# Modified_Dub_Siren.net
KiCad netlist of a schematic drawn in Altium Designer
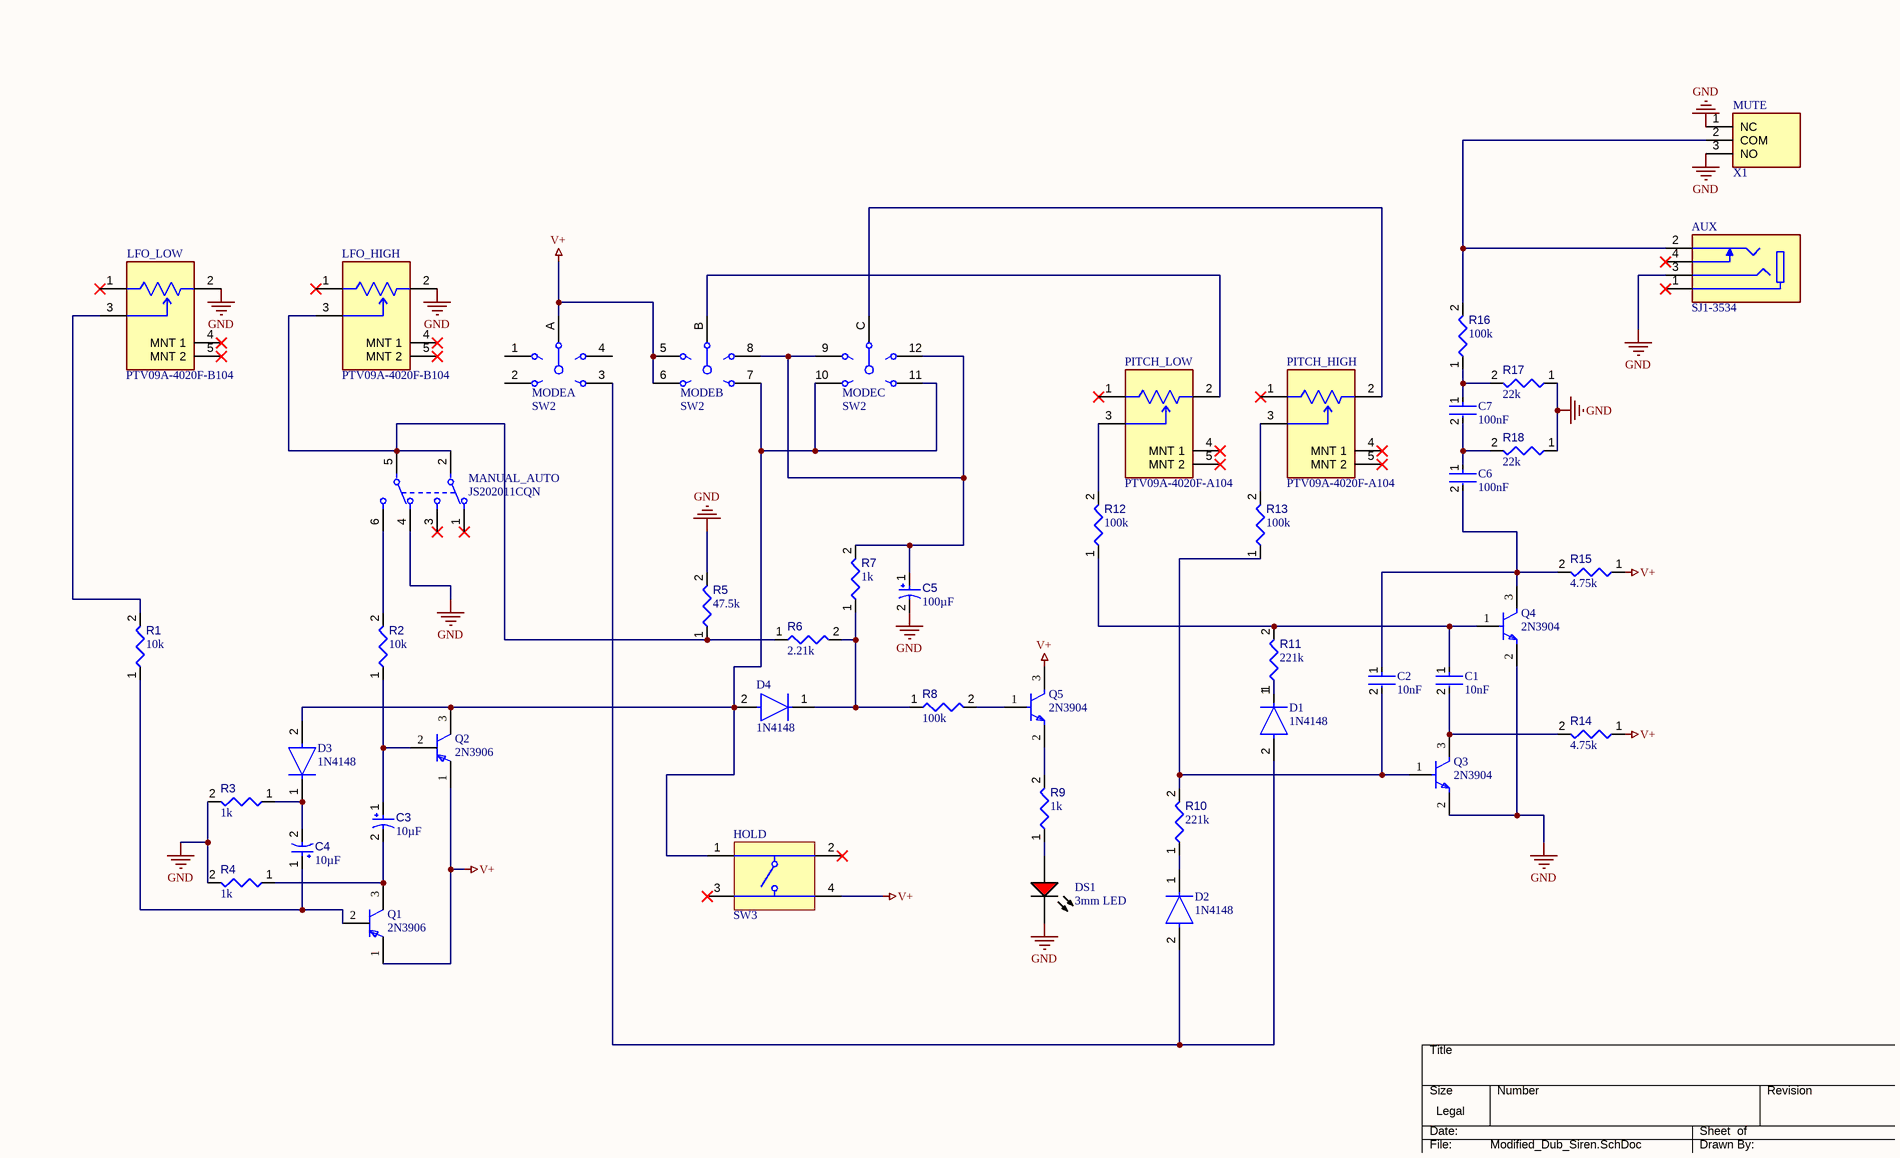
[diagram p0: Modified_Dub_Siren.SchDoc]

(export (version "E")
  (design (tool "Eeschema 10.0.6"))
  (components
    (comp (ref "AUX")
      (value "SJ1-3534")
      (footprint "CUI_SJ1-3533")
      (description "3.5 mm Right-Angle Stereo Jack, 4 Pin PCB Mount, Threaded w/ Nut")
      (fields (field (name "MF") "Same Sky"))
      (libsource (lib "SJ1-3534") (part "SJ1-3534"))
    )
    (comp (ref "C1")
      (value "10nF")
      (footprint "FP-K15H5-MFG")
      (description "CAP CER 0.1UF 50V X7R RADIAL")
      (fields (field (name "VOLTAGE") "50V") (field (name "TOLERANCE") "10%"))
      (libsource (lib "Altium Content Vault") (part "11868f565c42a9108669ba33697ecf6"))
    )
    (comp (ref "C2")
      (value "10nF")
      (footprint "FP-K15H5-MFG")
      (description "CAP CER 0.1UF 50V X7R RADIAL")
      (fields (field (name "VOLTAGE") "50V") (field (name "TOLERANCE") "10%"))
      (libsource (lib "Altium Content Vault") (part "11868f565c42a9108669ba33697ecf6"))
    )
    (comp (ref "C3")
      (value "10µF")
      (footprint "CAPPR55-200-1100X500X1200")
      (description "Aluminum Electrolytic Capacitor, 10 uF, +/- 20%, 50 V, -40 to 85 degC, 2-Pin THD, RoHS, Bulk")
      (fields (field (name "MANUFACTURER") "Panasonic") (field (name "TOLERANCE") "20%"))
      (libsource (lib "Brenna Kennedy-Moore") (part "CAP-P-2"))
    )
    (comp (ref "C4")
      (value "10µF")
      (footprint "CAPPR55-200-1100X500X1200")
      (description "Aluminum Electrolytic Capacitor, 10 uF, +/- 20%, 50 V, -40 to 85 degC, 2-Pin THD, RoHS, Bulk")
      (fields (field (name "MANUFACTURER") "Panasonic") (field (name "TOLERANCE") "20%"))
      (libsource (lib "") (part "CAP-P-2_1"))
    )
    (comp (ref "C5")
      (value "100µF")
      (footprint "CAPPR55-200-1100X500X1200")
      (description "Aluminum Electrolytic Capacitor, 10 uF, +/- 20%, 50 V, -40 to 85 degC, 2-Pin THD, RoHS, Bulk")
      (fields (field (name "MANUFACTURER") "Panasonic") (field (name "TOLERANCE") "20%"))
      (libsource (lib "Brenna Kennedy-Moore") (part "CAP-P-2"))
    )
    (comp (ref "C6")
      (value "100nF")
      (footprint "FP-K15H5-MFG")
      (description "CAP CER 0.1UF 50V X7R RADIAL")
      (fields (field (name "VOLTAGE") "50V") (field (name "TOLERANCE") "10%"))
      (libsource (lib "Altium Content Vault") (part "11868f565c42a9108669ba33697ecf6"))
    )
    (comp (ref "C7")
      (value "100nF")
      (footprint "FP-K15H5-MFG")
      (description "CAP CER 0.1UF 50V X7R RADIAL")
      (fields (field (name "VOLTAGE") "50V") (field (name "TOLERANCE") "10%"))
      (libsource (lib "Altium Content Vault") (part "11868f565c42a9108669ba33697ecf6"))
    )
    (comp (ref "D1")
      (value "1N4148")
      (footprint "FP-017AG-MFG")
      (description "DIODE GEN PURP 100V 200MA DO35")
      (fields (field (name "VOLTAGE") "100V"))
      (libsource (lib "Altium Content Vault") (part "d7152d700b627762746794eb795d46e"))
    )
    (comp (ref "D2")
      (value "1N4148")
      (footprint "FP-017AG-MFG")
      (description "DIODE GEN PURP 100V 200MA DO35")
      (fields (field (name "VOLTAGE") "100V"))
      (libsource (lib "Altium Content Vault") (part "d7152d700b627762746794eb795d46e"))
    )
    (comp (ref "D3")
      (value "1N4148")
      (footprint "FP-017AG-MFG")
      (description "DIODE GEN PURP 100V 200MA DO35")
      (fields (field (name "VOLTAGE") "100V"))
      (libsource (lib "Altium Content Vault") (part "d7152d700b627762746794eb795d46e"))
    )
    (comp (ref "D4")
      (value "1N4148")
      (footprint "FP-017AG-MFG")
      (description "DIODE GEN PURP 100V 200MA DO35")
      (fields (field (name "VOLTAGE") "100V"))
      (libsource (lib "Altium Content Vault") (part "d7152d700b627762746794eb795d46e"))
    )
    (comp (ref "DS1")
      (value "3mm LED")
      (footprint "LED-2P-2.28-3MM_A")
      (description "Red LED, 80 mW, 30 mA, -25 to 85 degC, 2-Pin THD")
      (fields (field (name "MANUFACTURER") "Shenzhen CGX"))
      (libsource (lib "Brenna Kennedy-Moore") (part "LED-RED-AK-2"))
    )
    (comp (ref "HOLD")
      (value "SW3")
      (footprint "BEST-TS-1109_V")
      (description "Tactile Switch, SPST, 12 V, 50 mA, -20 to 80 degC, 4-Pin THD")
      (fields (field (name "MANUFACTURER") "Shenzhen Best"))
      (libsource (lib "Brenna Kennedy-Moore") (part "SW-SPST-4_A"))
    )
    (comp (ref "LFO_HIGH")
      (value "PTV09A-4020F-B104")
      (footprint "FP-PTV09A-4020-MFG")
      (description "POT 20K OHM 1/20W CARBON LOG")
      (fields
        (field (name "TOLERANCE") "20%")
        (field (name "OCTOPART") "https://octopart.com/ptv09a-4020f-a203-bourns-1637636")
      )
      (libsource (lib "Altium Content Vault") (part "93b1c08ba1369577c2f09b47e9e292e"))
    )
    (comp (ref "LFO_LOW")
      (value "PTV09A-4020F-B104")
      (footprint "FP-PTV09A-4020-MFG")
      (description "POT 20K OHM 1/20W CARBON LOG")
      (fields
        (field (name "TOLERANCE") "20%")
        (field (name "OCTOPART") "https://octopart.com/ptv09a-4020f-a203-bourns-1637636")
      )
      (libsource (lib "Altium Content Vault") (part "93b1c08ba1369577c2f09b47e9e292e"))
    )
    (comp (ref "MANUAL_AUTO")
      (value "JS202011CQN")
      (footprint "FP-JS202011AQN-MFG")
      (description "SWITCH SLIDE DPDT 300MA 6V")
      (libsource (lib "Altium Content Vault") (part "a9e2ad50e97b660f430b512a9354c8c"))
    )
    (comp (ref "MODE")
      (value "SW2")
      (footprint "CKCP-A30415RNZQ-15_V")
      (description "A Series Rotary Switch, 3 Poles, 4 Positions, 30 deg Angle of Throw, -30 to 85 degC, RoHS")
      (fields (field (name "PARTNUMBER") "A30415RNZQE") (field (name "MANUFACTURER") "C&K Components"))
      (libsource (lib "Altium Content Vault") (part "CKCP-SW_3P4T-15"))
    )
    (comp (ref "MUTE")
      (value "X1")
      (footprint "100SP5T1B1M2QEH")
      (description "TOGGLE, 5A, 120VAC/28VDC SPDT, On-Off-(On) Panel Mount, Through Hole")
      (fields
        (field (name "MANUFACTURER_PART_NUMBER") "100SP5T1B1M2QEH")
        (field (name "MOUSER PART NUMBER") "612-100-E1121")
      )
      (libsource (lib "100SP5T1B1M2QEH") (part "100SP5T1B1M2QEH"))
    )
    (comp (ref "PITCH_HIGH")
      (value "PTV09A-4020F-A104")
      (footprint "FP-PTV09A-4020-MFG")
      (description "POT 20K OHM 1/20W CARBON LOG")
      (fields
        (field (name "TOLERANCE") "20%")
        (field (name "OCTOPART") "https://octopart.com/ptv09a-4020f-a203-bourns-1637636")
      )
      (libsource (lib "Altium Content Vault") (part "93b1c08ba1369577c2f09b47e9e292e"))
    )
    (comp (ref "PITCH_LOW")
      (value "PTV09A-4020F-A104")
      (footprint "FP-PTV09A-4020-MFG")
      (description "POT 20K OHM 1/20W CARBON LOG")
      (fields
        (field (name "TOLERANCE") "20%")
        (field (name "OCTOPART") "https://octopart.com/ptv09a-4020f-a203-bourns-1637636")
      )
      (libsource (lib "Altium Content Vault") (part "93b1c08ba1369577c2f09b47e9e292e"))
    )
    (comp (ref "Q1")
      (value "2N3906")
      (footprint "FP-135AR-MFG")
      (description "2N3906TF Small Signal Bipolar Transistor, 0.2A I(C), 40V V(BR)CEO, 1-Element, PNP, Silicon, TO-92")
      (libsource (lib "Altium Content Vault") (part "40d2b7e180a7bcff784209620afba3e"))
    )
    (comp (ref "Q2")
      (value "2N3906")
      (footprint "FP-135AR-MFG")
      (description "2N3906TF Small Signal Bipolar Transistor, 0.2A I(C), 40V V(BR)CEO, 1-Element, PNP, Silicon, TO-92")
      (libsource (lib "Altium Content Vault") (part "40d2b7e180a7bcff784209620afba3e"))
    )
    (comp (ref "Q3")
      (value "2N3904")
      (footprint "FP-135AR-MFG")
      (description "KSP10TA Transistor, bjt, npn, 25V V(Br)Ceo, to-92 Rohs Compliant: Yes")
      (libsource (lib "Altium Content Vault") (part "b44e953556f554d0102664c7d152cb4"))
    )
    (comp (ref "Q4")
      (value "2N3904")
      (footprint "FP-135AR-MFG")
      (description "KSP10TA Transistor, bjt, npn, 25V V(Br)Ceo, to-92 Rohs Compliant: Yes")
      (libsource (lib "Altium Content Vault") (part "b44e953556f554d0102664c7d152cb4"))
    )
    (comp (ref "Q5")
      (value "2N3904")
      (footprint "FP-135AR-MFG")
      (description "KSP10TA Transistor, bjt, npn, 25V V(Br)Ceo, to-92 Rohs Compliant: Yes")
      (libsource (lib "Altium Content Vault") (part "b44e953556f554d0102664c7d152cb4"))
    )
    (comp (ref "R1")
      (value "10k")
      (footprint "RESA60-630X240")
      (description "Axial Resistor, 10 KOhm, +/- 1%, 0.25 W, -55 to 155 degC, 2-Pin THD, RoHS, Bulk")
      (fields (field (name "POWER") "250mW") (field (name "TOLERANCE") "1%"))
      (libsource (lib "Brenna Kennedy-Moore") (part "RES-2"))
    )
    (comp (ref "R2")
      (value "10k")
      (footprint "RESA60-630X240")
      (description "Axial Resistor, 10 KOhm, +/- 1%, 0.25 W, -55 to 155 degC, 2-Pin THD, RoHS, Bulk")
      (fields (field (name "POWER") "250mW") (field (name "TOLERANCE") "1%"))
      (libsource (lib "Brenna Kennedy-Moore") (part "RES-2"))
    )
    (comp (ref "R3")
      (value "1k")
      (footprint "RESA60-630X240")
      (description "Axial Resistor, 1 KOhm, +/- 1%, 250 mW, -55 to 155 degC, 2-Pin THD, RoHS, Bulk")
      (fields (field (name "POWER") "250mW") (field (name "TOLERANCE") "1%"))
      (libsource (lib "Brenna Kennedy-Moore") (part "RES-2"))
    )
    (comp (ref "R4")
      (value "1k")
      (footprint "RESA60-630X240")
      (description "Axial Resistor, 1 KOhm, +/- 1%, 250 mW, -55 to 155 degC, 2-Pin THD, RoHS, Bulk")
      (fields (field (name "POWER") "250mW") (field (name "TOLERANCE") "1%"))
      (libsource (lib "Brenna Kennedy-Moore") (part "RES-2"))
    )
    (comp (ref "R5")
      (value "47.5k")
      (footprint "RESA60-630X240")
      (description "Axial Resistor, 47.5 KOhm, +/- 1%, 0.25 W, -55 to 155 degC, 2-Pin THD, RoHS, Bulk")
      (fields (field (name "POWER") "250mW") (field (name "TOLERANCE") "1%"))
      (libsource (lib "Brenna Kennedy-Moore") (part "RES-2"))
    )
    (comp (ref "R6")
      (value "2.21k")
      (footprint "RESA60-630X240")
      (description "Axial Resistor, 2.21 KOhm, +/- 1%, 0.25 W, -55 to 155 degC, 2-Pin THD, RoHS, Bulk")
      (fields (field (name "POWER") "250mW") (field (name "TOLERANCE") "1%"))
      (libsource (lib "Brenna Kennedy-Moore") (part "RES-2"))
    )
    (comp (ref "R7")
      (value "1k")
      (footprint "RESA60-630X240")
      (description "Axial Resistor, 1 KOhm, +/- 1%, 250 mW, -55 to 155 degC, 2-Pin THD, RoHS, Bulk")
      (fields (field (name "POWER") "250mW") (field (name "TOLERANCE") "1%"))
      (libsource (lib "Brenna Kennedy-Moore") (part "RES-2"))
    )
    (comp (ref "R8")
      (value "100k")
      (footprint "RESA60-630X240")
      (description "Axial Resistor, 100 KOhm, +/- 1%, 0.25 W, -55 to 155 degC, 2-Pin THD, RoHS, Bulk")
      (fields (field (name "POWER") "250mW") (field (name "TOLERANCE") "1%"))
      (libsource (lib "Brenna Kennedy-Moore") (part "RES-2"))
    )
    (comp (ref "R9")
      (value "1k")
      (footprint "RESA60-630X240")
      (description "Axial Resistor, 1 KOhm, +/- 1%, 250 mW, -55 to 155 degC, 2-Pin THD, RoHS, Bulk")
      (fields (field (name "POWER") "250mW") (field (name "TOLERANCE") "1%"))
      (libsource (lib "Brenna Kennedy-Moore") (part "RES-2"))
    )
    (comp (ref "R10")
      (value "221k")
      (footprint "RESA60-630X240")
      (description "Axial Resistor, 221 KOhm, +/- 1%, 0.25 W, -55 to 155 degC, 2-Pin THD, RoHS, Bulk")
      (fields (field (name "POWER") "250mW") (field (name "TOLERANCE") "1%"))
      (libsource (lib "Brenna Kennedy-Moore") (part "RES-2"))
    )
    (comp (ref "R11")
      (value "221k")
      (footprint "RESA60-630X240")
      (description "Axial Resistor, 221 KOhm, +/- 1%, 0.25 W, -55 to 155 degC, 2-Pin THD, RoHS, Bulk")
      (fields (field (name "POWER") "250mW") (field (name "TOLERANCE") "1%"))
      (libsource (lib "Brenna Kennedy-Moore") (part "RES-2"))
    )
    (comp (ref "R12")
      (value "100k")
      (footprint "RESA60-630X240")
      (description "Axial Resistor, 100 KOhm, +/- 1%, 0.25 W, -55 to 155 degC, 2-Pin THD, RoHS, Bulk")
      (fields (field (name "POWER") "250mW") (field (name "TOLERANCE") "1%"))
      (libsource (lib "Brenna Kennedy-Moore") (part "RES-2"))
    )
    (comp (ref "R13")
      (value "100k")
      (footprint "RESA60-630X240")
      (description "Axial Resistor, 100 KOhm, +/- 1%, 0.25 W, -55 to 155 degC, 2-Pin THD, RoHS, Bulk")
      (fields (field (name "POWER") "250mW") (field (name "TOLERANCE") "1%"))
      (libsource (lib "Brenna Kennedy-Moore") (part "RES-2"))
    )
    (comp (ref "R14")
      (value "4.75k")
      (footprint "RESA60-630X240")
      (description "Axial Resistor, 4.75 KOhm, +/- 1%, 0.25 W, -55 to 155 degC, 2-Pin THD, RoHS, Bulk")
      (fields (field (name "POWER") "250mW") (field (name "TOLERANCE") "1%"))
      (libsource (lib "Brenna Kennedy-Moore") (part "RES-2"))
    )
    (comp (ref "R15")
      (value "4.75k")
      (footprint "RESA60-630X240")
      (description "Axial Resistor, 4.75 KOhm, +/- 1%, 0.25 W, -55 to 155 degC, 2-Pin THD, RoHS, Bulk")
      (fields (field (name "POWER") "250mW") (field (name "TOLERANCE") "1%"))
      (libsource (lib "Brenna Kennedy-Moore") (part "RES-2"))
    )
    (comp (ref "R16")
      (value "100k")
      (footprint "RESA60-630X240")
      (description "Axial Resistor, 100 KOhm, +/- 1%, 0.25 W, -55 to 155 degC, 2-Pin THD, RoHS, Bulk")
      (fields (field (name "POWER") "250mW") (field (name "TOLERANCE") "1%"))
      (libsource (lib "Brenna Kennedy-Moore") (part "RES-2"))
    )
    (comp (ref "R17")
      (value "22k")
      (footprint "RESA60-630X240")
      (description "Axial Resistor, 22.1 KOhm, +/- 1%, 0.25 W, -55 to 155 degC, 2-Pin THD, RoHS, Bulk")
      (fields (field (name "POWER") "250mW") (field (name "TOLERANCE") "1%"))
      (libsource (lib "Brenna Kennedy-Moore") (part "RES-2"))
    )
    (comp (ref "R18")
      (value "22k")
      (footprint "RESA60-630X240")
      (description "Axial Resistor, 22.1 KOhm, +/- 1%, 0.25 W, -55 to 155 degC, 2-Pin THD, RoHS, Bulk")
      (fields (field (name "POWER") "250mW") (field (name "TOLERANCE") "1%"))
      (libsource (lib "Brenna Kennedy-Moore") (part "RES-2"))
    )
  )
  (nets
    (net (code "1") (name "GND") (class "Default")
      (node (ref "AUX") (pin "3") (pinfunction "3_3") (pintype "passive"))
      (node (ref "C5") (pin "2") (pinfunction "2_2") (pintype "passive"))
      (node (ref "DS1") (pin "2") (pinfunction "K_2") (pintype "passive"))
      (node (ref "LFO_HIGH") (pin "2") (pinfunction "2_2") (pintype "passive"))
      (node (ref "LFO_LOW") (pin "2") (pinfunction "2_2") (pintype "passive"))
      (node (ref "MANUAL_AUTO") (pin "4") (pinfunction "4_4") (pintype "passive"))
      (node (ref "MUTE") (pin "1") (pinfunction "NC_1") (pintype "passive"))
      (node (ref "MUTE") (pin "3") (pinfunction "NO_3") (pintype "passive"))
      (node (ref "Q3") (pin "2") (pinfunction "E_2") (pintype "passive"))
      (node (ref "Q4") (pin "2") (pinfunction "E_2") (pintype "passive"))
      (node (ref "R17") (pin "1") (pinfunction "1_1") (pintype "passive"))
      (node (ref "R18") (pin "1") (pinfunction "1_1") (pintype "passive"))
      (node (ref "R3") (pin "2") (pinfunction "2_2") (pintype "passive"))
      (node (ref "R4") (pin "2") (pinfunction "2_2") (pintype "passive"))
      (node (ref "R5") (pin "2") (pinfunction "2_2") (pintype "passive"))
    )
    (net (code "2") (name "Net-(C5-Pad1)") (class "Default")
      (node (ref "C5") (pin "1") (pinfunction "1_1") (pintype "passive"))
      (node (ref "MODE") (pin "12") (pinfunction "12_12") (pintype "passive"))
      (node (ref "MODE") (pin "8") (pinfunction "8_8") (pintype "passive"))
      (node (ref "MODE") (pin "9") (pinfunction "9_9") (pintype "passive"))
      (node (ref "R7") (pin "2") (pinfunction "2_2") (pintype "passive"))
    )
    (net (code "3") (name "Net-(C6-Pad1)") (class "Default")
      (node (ref "C6") (pin "1") (pinfunction "1_1") (pintype "passive"))
      (node (ref "C7") (pin "2") (pinfunction "2_2") (pintype "passive"))
      (node (ref "R18") (pin "2") (pinfunction "2_2") (pintype "passive"))
    )
    (net (code "4") (name "Net-(C7-Pad1)") (class "Default")
      (node (ref "C7") (pin "1") (pinfunction "1_1") (pintype "passive"))
      (node (ref "R16") (pin "1") (pinfunction "1_1") (pintype "passive"))
      (node (ref "R17") (pin "2") (pinfunction "2_2") (pintype "passive"))
    )
    (net (code "5") (name "Net-(D1-A)") (class "Default")
      (node (ref "D1") (pin "2") (pinfunction "A_2") (pintype "passive"))
      (node (ref "D2") (pin "2") (pinfunction "A_2") (pintype "passive"))
      (node (ref "MODE") (pin "3") (pinfunction "3_3") (pintype "passive"))
    )
    (net (code "6") (name "Net-(D1-C)") (class "Default")
      (node (ref "D1") (pin "1") (pinfunction "C_1") (pintype "passive"))
      (node (ref "R11") (pin "1") (pinfunction "1_1") (pintype "passive"))
    )
    (net (code "7") (name "Net-(D2-C)") (class "Default")
      (node (ref "D2") (pin "1") (pinfunction "C_1") (pintype "passive"))
      (node (ref "R10") (pin "1") (pinfunction "1_1") (pintype "passive"))
    )
    (net (code "8") (name "Net-(D3-A)") (class "Default")
      (node (ref "D3") (pin "2") (pinfunction "A_2") (pintype "passive"))
      (node (ref "D4") (pin "2") (pinfunction "A_2") (pintype "passive"))
      (node (ref "HOLD") (pin "1") (pinfunction "1_1") (pintype "passive"))
      (node (ref "MODE") (pin "10") (pinfunction "10_10") (pintype "passive"))
      (node (ref "MODE") (pin "11") (pinfunction "11_11") (pintype "passive"))
      (node (ref "MODE") (pin "7") (pinfunction "7_7") (pintype "passive"))
      (node (ref "Q2") (pin "3") (pinfunction "C_3") (pintype "passive"))
    )
    (net (code "9") (name "Net-(D3-C)") (class "Default")
      (node (ref "C4") (pin "2") (pinfunction "2_2") (pintype "passive"))
      (node (ref "D3") (pin "1") (pinfunction "C_1") (pintype "passive"))
      (node (ref "R3") (pin "1") (pinfunction "1_1") (pintype "passive"))
    )
    (net (code "10") (name "Net-(D4-C)") (class "Default")
      (node (ref "D4") (pin "1") (pinfunction "C_1") (pintype "passive"))
      (node (ref "R6") (pin "2") (pinfunction "2_2") (pintype "passive"))
      (node (ref "R7") (pin "1") (pinfunction "1_1") (pintype "passive"))
      (node (ref "R8") (pin "1") (pinfunction "1_1") (pintype "passive"))
    )
    (net (code "11") (name "Net-(DS1-A)") (class "Default")
      (node (ref "DS1") (pin "1") (pinfunction "A_1") (pintype "passive"))
      (node (ref "R9") (pin "1") (pinfunction "1_1") (pintype "passive"))
    )
    (net (code "12") (name "Net-(LFO_HIGH-Pad3)") (class "Default")
      (node (ref "LFO_HIGH") (pin "3") (pinfunction "3_3") (pintype "passive"))
      (node (ref "MANUAL_AUTO") (pin "2") (pinfunction "2_2") (pintype "passive"))
      (node (ref "MANUAL_AUTO") (pin "5") (pinfunction "5_5") (pintype "passive"))
      (node (ref "R5") (pin "1") (pinfunction "1_1") (pintype "passive"))
      (node (ref "R6") (pin "1") (pinfunction "1_1") (pintype "passive"))
    )
    (net (code "13") (name "Net-(LFO_LOW-Pad3)") (class "Default")
      (node (ref "LFO_LOW") (pin "3") (pinfunction "3_3") (pintype "passive"))
      (node (ref "R1") (pin "2") (pinfunction "2_2") (pintype "passive"))
    )
    (net (code "14") (name "Net-(MANUAL_AUTO-Pad6)") (class "Default")
      (node (ref "MANUAL_AUTO") (pin "6") (pinfunction "6_6") (pintype "passive"))
      (node (ref "R2") (pin "2") (pinfunction "2_2") (pintype "passive"))
    )
    (net (code "15") (name "Net-(MODE-PadB)") (class "Default")
      (node (ref "MODE") (pin "B") (pinfunction "B_B") (pintype "passive"))
      (node (ref "PITCH_LOW") (pin "2") (pinfunction "2_2") (pintype "passive"))
    )
    (net (code "16") (name "Net-(MODE-PadC)") (class "Default")
      (node (ref "MODE") (pin "C") (pinfunction "C_C") (pintype "passive"))
      (node (ref "PITCH_HIGH") (pin "2") (pinfunction "2_2") (pintype "passive"))
    )
    (net (code "17") (name "Net-(MUTE-COM)") (class "Default")
      (node (ref "AUX") (pin "2") (pinfunction "2_2") (pintype "passive"))
      (node (ref "MUTE") (pin "2") (pinfunction "COM_2") (pintype "passive"))
      (node (ref "R16") (pin "2") (pinfunction "2_2") (pintype "passive"))
    )
    (net (code "18") (name "Net-(PITCH_HIGH-Pad3)") (class "Default")
      (node (ref "PITCH_HIGH") (pin "3") (pinfunction "3_3") (pintype "passive"))
      (node (ref "R13") (pin "2") (pinfunction "2_2") (pintype "passive"))
    )
    (net (code "19") (name "Net-(PITCH_LOW-Pad3)") (class "Default")
      (node (ref "PITCH_LOW") (pin "3") (pinfunction "3_3") (pintype "passive"))
      (node (ref "R12") (pin "2") (pinfunction "2_2") (pintype "passive"))
    )
    (net (code "20") (name "Net-(Q1-B)") (class "Default")
      (node (ref "C4") (pin "1") (pinfunction "1_1") (pintype "passive"))
      (node (ref "Q1") (pin "2") (pinfunction "B_2") (pintype "passive"))
      (node (ref "R1") (pin "1") (pinfunction "1_1") (pintype "passive"))
    )
    (net (code "21") (name "Net-(Q1-C)") (class "Default")
      (node (ref "C3") (pin "2") (pinfunction "2_2") (pintype "passive"))
      (node (ref "Q1") (pin "3") (pinfunction "C_3") (pintype "passive"))
      (node (ref "R4") (pin "1") (pinfunction "1_1") (pintype "passive"))
    )
    (net (code "22") (name "Net-(Q2-B)") (class "Default")
      (node (ref "C3") (pin "1") (pinfunction "1_1") (pintype "passive"))
      (node (ref "Q2") (pin "2") (pinfunction "B_2") (pintype "passive"))
      (node (ref "R2") (pin "1") (pinfunction "1_1") (pintype "passive"))
    )
    (net (code "23") (name "Net-(Q3-B)") (class "Default")
      (node (ref "C2") (pin "2") (pinfunction "2_2") (pintype "passive"))
      (node (ref "Q3") (pin "1") (pinfunction "B_1") (pintype "passive"))
      (node (ref "R10") (pin "2") (pinfunction "2_2") (pintype "passive"))
      (node (ref "R13") (pin "1") (pinfunction "1_1") (pintype "passive"))
    )
    (net (code "24") (name "Net-(Q3-C)") (class "Default")
      (node (ref "C1") (pin "2") (pinfunction "2_2") (pintype "passive"))
      (node (ref "Q3") (pin "3") (pinfunction "C_3") (pintype "passive"))
      (node (ref "R14") (pin "2") (pinfunction "2_2") (pintype "passive"))
    )
    (net (code "25") (name "Net-(Q4-B)") (class "Default")
      (node (ref "C1") (pin "1") (pinfunction "1_1") (pintype "passive"))
      (node (ref "Q4") (pin "1") (pinfunction "B_1") (pintype "passive"))
      (node (ref "R11") (pin "2") (pinfunction "2_2") (pintype "passive"))
      (node (ref "R12") (pin "1") (pinfunction "1_1") (pintype "passive"))
    )
    (net (code "26") (name "Net-(Q4-C)") (class "Default")
      (node (ref "C2") (pin "1") (pinfunction "1_1") (pintype "passive"))
      (node (ref "C6") (pin "2") (pinfunction "2_2") (pintype "passive"))
      (node (ref "Q4") (pin "3") (pinfunction "C_3") (pintype "passive"))
      (node (ref "R15") (pin "2") (pinfunction "2_2") (pintype "passive"))
    )
    (net (code "27") (name "Net-(Q5-B)") (class "Default")
      (node (ref "Q5") (pin "1") (pinfunction "B_1") (pintype "passive"))
      (node (ref "R8") (pin "2") (pinfunction "2_2") (pintype "passive"))
    )
    (net (code "28") (name "Net-(Q5-E)") (class "Default")
      (node (ref "Q5") (pin "2") (pinfunction "E_2") (pintype "passive"))
      (node (ref "R9") (pin "2") (pinfunction "2_2") (pintype "passive"))
    )
    (net (code "29") (name "V+") (class "Default")
      (node (ref "HOLD") (pin "4") (pinfunction "4_4") (pintype "passive"))
      (node (ref "MODE") (pin "5") (pinfunction "5_5") (pintype "passive"))
      (node (ref "MODE") (pin "6") (pinfunction "6_6") (pintype "passive"))
      (node (ref "MODE") (pin "A") (pinfunction "A_A") (pintype "passive"))
      (node (ref "Q1") (pin "1") (pinfunction "E_1") (pintype "passive"))
      (node (ref "Q2") (pin "1") (pinfunction "E_1") (pintype "passive"))
      (node (ref "Q5") (pin "3") (pinfunction "C_3") (pintype "passive"))
      (node (ref "R14") (pin "1") (pinfunction "1_1") (pintype "passive"))
      (node (ref "R15") (pin "1") (pinfunction "1_1") (pintype "passive"))
    )
    (net (code "30") (name "unconnected-(AUX-Pad1)") (class "Default")
      (node (ref "AUX") (pin "1") (pinfunction "1_1") (pintype "passive+no_connect"))
    )
    (net (code "31") (name "unconnected-(AUX-Pad4)") (class "Default")
      (node (ref "AUX") (pin "4") (pinfunction "4_4") (pintype "passive+no_connect"))
    )
    (net (code "32") (name "unconnected-(HOLD-Pad2)") (class "Default")
      (node (ref "HOLD") (pin "2") (pinfunction "2_2") (pintype "passive+no_connect"))
    )
    (net (code "33") (name "unconnected-(HOLD-Pad3)") (class "Default")
      (node (ref "HOLD") (pin "3") (pinfunction "3_3") (pintype "passive+no_connect"))
    )
    (net (code "34") (name "unconnected-(LFO_HIGH-MNT_1-Pad4)") (class "Default")
      (node (ref "LFO_HIGH") (pin "4") (pinfunction "MNT_1_4") (pintype "passive+no_connect"))
    )
    (net (code "35") (name "unconnected-(LFO_HIGH-MNT_2-Pad5)") (class "Default")
      (node (ref "LFO_HIGH") (pin "5") (pinfunction "MNT_2_5") (pintype "passive+no_connect"))
    )
    (net (code "36") (name "unconnected-(LFO_HIGH-Pad1)") (class "Default")
      (node (ref "LFO_HIGH") (pin "1") (pinfunction "1_1") (pintype "passive+no_connect"))
    )
    (net (code "37") (name "unconnected-(LFO_LOW-MNT_1-Pad4)") (class "Default")
      (node (ref "LFO_LOW") (pin "4") (pinfunction "MNT_1_4") (pintype "passive+no_connect"))
    )
    (net (code "38") (name "unconnected-(LFO_LOW-MNT_2-Pad5)") (class "Default")
      (node (ref "LFO_LOW") (pin "5") (pinfunction "MNT_2_5") (pintype "passive+no_connect"))
    )
    (net (code "39") (name "unconnected-(LFO_LOW-Pad1)") (class "Default")
      (node (ref "LFO_LOW") (pin "1") (pinfunction "1_1") (pintype "passive+no_connect"))
    )
    (net (code "40") (name "unconnected-(MANUAL_AUTO-Pad1)") (class "Default")
      (node (ref "MANUAL_AUTO") (pin "1") (pinfunction "1_1") (pintype "passive+no_connect"))
    )
    (net (code "41") (name "unconnected-(MANUAL_AUTO-Pad3)") (class "Default")
      (node (ref "MANUAL_AUTO") (pin "3") (pinfunction "3_3") (pintype "passive+no_connect"))
    )
    (net (code "42") (name "unconnected-(MODE-Pad1)") (class "Default")
      (node (ref "MODE") (pin "1") (pinfunction "1_1") (pintype "passive"))
    )
    (net (code "43") (name "unconnected-(MODE-Pad2)") (class "Default")
      (node (ref "MODE") (pin "2") (pinfunction "2_2") (pintype "passive"))
    )
    (net (code "44") (name "unconnected-(MODE-Pad4)") (class "Default")
      (node (ref "MODE") (pin "4") (pinfunction "4_4") (pintype "passive"))
    )
    (net (code "45") (name "unconnected-(PITCH_HIGH-MNT_1-Pad4)") (class "Default")
      (node (ref "PITCH_HIGH") (pin "4") (pinfunction "MNT_1_4") (pintype "passive+no_connect"))
    )
    (net (code "46") (name "unconnected-(PITCH_HIGH-MNT_2-Pad5)") (class "Default")
      (node (ref "PITCH_HIGH") (pin "5") (pinfunction "MNT_2_5") (pintype "passive+no_connect"))
    )
    (net (code "47") (name "unconnected-(PITCH_HIGH-Pad1)") (class "Default")
      (node (ref "PITCH_HIGH") (pin "1") (pinfunction "1_1") (pintype "passive+no_connect"))
    )
    (net (code "48") (name "unconnected-(PITCH_LOW-MNT_1-Pad4)") (class "Default")
      (node (ref "PITCH_LOW") (pin "4") (pinfunction "MNT_1_4") (pintype "passive+no_connect"))
    )
    (net (code "49") (name "unconnected-(PITCH_LOW-MNT_2-Pad5)") (class "Default")
      (node (ref "PITCH_LOW") (pin "5") (pinfunction "MNT_2_5") (pintype "passive+no_connect"))
    )
    (net (code "50") (name "unconnected-(PITCH_LOW-Pad1)") (class "Default")
      (node (ref "PITCH_LOW") (pin "1") (pinfunction "1_1") (pintype "passive+no_connect"))
    )
  )
)
